# Micro_RC_Receiver.net
KiCad netlist of a schematic drawn in EAGLE
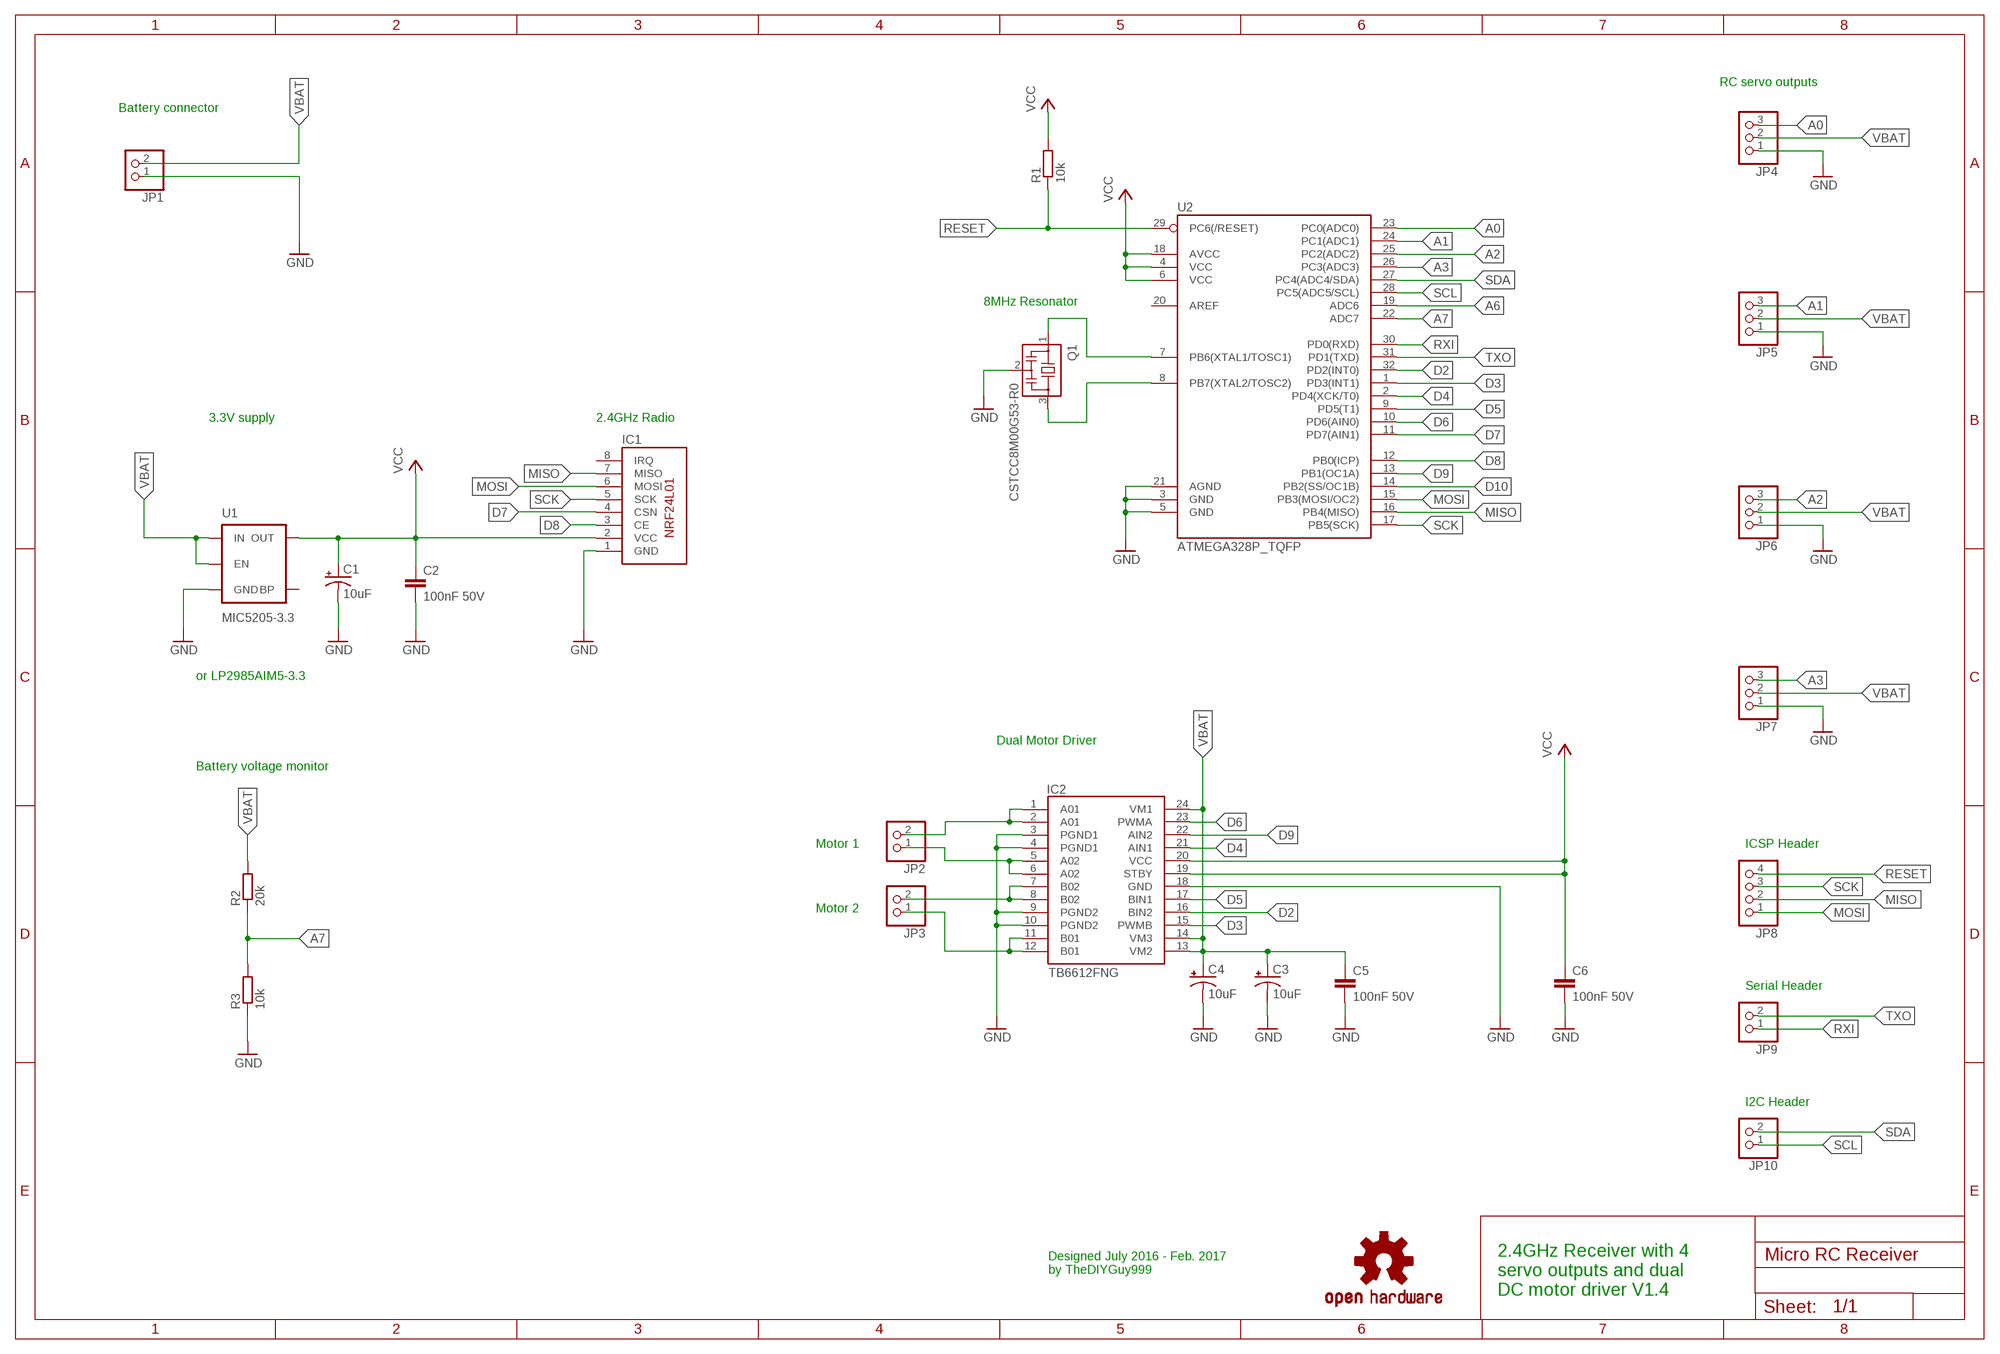
[diagram p0: schematic, sheet 1]

(export (version "E")
  (design (tool "Eeschema 10.0.6"))
  (components
    (comp (ref "C1")
      (value "10uF")
      (footprint "eagle-import:EIA3216")
      (libsource (lib "eagle-import") (part "10UF-16V-10%(TANT)"))
    )
    (comp (ref "C2")
      (value "100nF 50V")
      (footprint "eagle-import:C0805")
      (libsource (lib "eagle-import") (part "C-EUC0805"))
    )
    (comp (ref "C3")
      (value "10uF")
      (footprint "eagle-import:EIA3216")
      (libsource (lib "eagle-import") (part "10UF-16V-10%(TANT)"))
    )
    (comp (ref "C4")
      (value "10uF")
      (footprint "eagle-import:EIA3216")
      (libsource (lib "eagle-import") (part "10UF-16V-10%(TANT)"))
    )
    (comp (ref "C5")
      (value "100nF 50V")
      (footprint "eagle-import:C0805")
      (libsource (lib "eagle-import") (part "C-EUC0805"))
    )
    (comp (ref "C6")
      (value "100nF 50V")
      (footprint "eagle-import:C0805")
      (libsource (lib "eagle-import") (part "C-EUC0805"))
    )
    (comp (ref "IC1")
      (value "NRF24L01SMD")
      (footprint "eagle-import:NRF24L01_SMD")
      (libsource (lib "eagle-import") (part "NRF24L01SMD"))
    )
    (comp (ref "IC2")
      (value "TB6612FNG")
      (footprint "eagle-import:SSOP24")
      (libsource (lib "eagle-import") (part "TB6612FNG"))
    )
    (comp (ref "JP1")
      (value "PINHD-1X2")
      (footprint "eagle-import:1X02")
      (libsource (lib "eagle-import") (part "PINHD-1X2"))
    )
    (comp (ref "JP2")
      (value "PINHD-1X2")
      (footprint "eagle-import:1X02")
      (libsource (lib "eagle-import") (part "PINHD-1X2"))
    )
    (comp (ref "JP3")
      (value "PINHD-1X2")
      (footprint "eagle-import:1X02")
      (libsource (lib "eagle-import") (part "PINHD-1X2"))
    )
    (comp (ref "JP4")
      (value "PINHD-1X3")
      (footprint "eagle-import:1X03")
      (libsource (lib "eagle-import") (part "PINHD-1X3"))
    )
    (comp (ref "JP5")
      (value "PINHD-1X3")
      (footprint "eagle-import:1X03")
      (libsource (lib "eagle-import") (part "PINHD-1X3"))
    )
    (comp (ref "JP6")
      (value "PINHD-1X3")
      (footprint "eagle-import:1X03")
      (libsource (lib "eagle-import") (part "PINHD-1X3"))
    )
    (comp (ref "JP7")
      (value "PINHD-1X3")
      (footprint "eagle-import:1X03")
      (libsource (lib "eagle-import") (part "PINHD-1X3"))
    )
    (comp (ref "JP8")
      (value "PINHD-1X4")
      (footprint "eagle-import:1X04")
      (libsource (lib "eagle-import") (part "PINHD-1X4"))
    )
    (comp (ref "JP9")
      (value "PINHD-1X2")
      (footprint "eagle-import:1X02")
      (libsource (lib "eagle-import") (part "PINHD-1X2"))
    )
    (comp (ref "JP10")
      (value "PINHD-1X2")
      (footprint "eagle-import:1X02")
      (libsource (lib "eagle-import") (part "PINHD-1X2"))
    )
    (comp (ref "LOGO1")
      (value "OSHW-LOGOS")
      (footprint "eagle-import:OSHW-LOGO-S")
      (libsource (lib "eagle-import") (part "OSHW-LOGOS"))
    )
    (comp (ref "Q1")
      (value "CSTCC8M00G53-R0")
      (footprint "eagle-import:CSTCC")
      (libsource (lib "eagle-import") (part "CSTCC8M00G53-R0"))
    )
    (comp (ref "R1")
      (value "10k")
      (footprint "eagle-import:R0805")
      (libsource (lib "eagle-import") (part "R-EU_R0805"))
    )
    (comp (ref "R2")
      (value "20k")
      (footprint "eagle-import:R0805")
      (libsource (lib "eagle-import") (part "R-EU_R0805"))
    )
    (comp (ref "R3")
      (value "10k")
      (footprint "eagle-import:R0805")
      (libsource (lib "eagle-import") (part "R-EU_R0805"))
    )
    (comp (ref "U1")
      (value "MIC5205-3.3")
      (footprint "eagle-import:SOT23-5")
      (libsource (lib "eagle-import") (part "MIC52053.3V"))
    )
    (comp (ref "U2")
      (value "ATMEGA328P_TQFP")
      (footprint "eagle-import:TQFP32-08")
      (libsource (lib "eagle-import") (part "ATMEGA328P_TQFP"))
    )
  )
  (nets
    (net (code "1") (name "A0") (class "Default")
      (node (ref "JP4") (pin "3") (pinfunction "3_3") (pintype "passive"))
      (node (ref "U2") (pin "23") (pinfunction "PC0(ADC0)_23") (pintype "bidirectional"))
    )
    (net (code "2") (name "A1") (class "Default")
      (node (ref "JP5") (pin "3") (pinfunction "3_3") (pintype "passive"))
      (node (ref "U2") (pin "24") (pinfunction "PC1(ADC1)_24") (pintype "bidirectional"))
    )
    (net (code "3") (name "A2") (class "Default")
      (node (ref "JP6") (pin "3") (pinfunction "3_3") (pintype "passive"))
      (node (ref "U2") (pin "25") (pinfunction "PC2(ADC2)_25") (pintype "bidirectional"))
    )
    (net (code "4") (name "A3") (class "Default")
      (node (ref "JP7") (pin "3") (pinfunction "3_3") (pintype "passive"))
      (node (ref "U2") (pin "26") (pinfunction "PC3(ADC3)_26") (pintype "bidirectional"))
    )
    (net (code "5") (name "A6") (class "Default")
      (node (ref "U2") (pin "19") (pinfunction "ADC6_19") (pintype "bidirectional"))
    )
    (net (code "6") (name "A7") (class "Default")
      (node (ref "R2") (pin "1") (pinfunction "1_1") (pintype "passive"))
      (node (ref "R3") (pin "2") (pinfunction "2_2") (pintype "passive"))
      (node (ref "U2") (pin "22") (pinfunction "ADC7_22") (pintype "bidirectional"))
    )
    (net (code "7") (name "D2") (class "Default")
      (node (ref "IC2") (pin "16") (pinfunction "BIN2_16") (pintype "bidirectional"))
      (node (ref "U2") (pin "32") (pinfunction "PD2(INT0)_32") (pintype "bidirectional"))
    )
    (net (code "8") (name "D3") (class "Default")
      (node (ref "IC2") (pin "15") (pinfunction "PWMB_15") (pintype "bidirectional"))
      (node (ref "U2") (pin "1") (pinfunction "PD3(INT1)_1") (pintype "bidirectional"))
    )
    (net (code "9") (name "D4") (class "Default")
      (node (ref "IC2") (pin "21") (pinfunction "AIN1_21") (pintype "bidirectional"))
      (node (ref "U2") (pin "2") (pinfunction "PD4(XCK/T0)_2") (pintype "bidirectional"))
    )
    (net (code "10") (name "D5") (class "Default")
      (node (ref "IC2") (pin "17") (pinfunction "BIN1_17") (pintype "bidirectional"))
      (node (ref "U2") (pin "9") (pinfunction "PD5(T1)_9") (pintype "bidirectional"))
    )
    (net (code "11") (name "D6") (class "Default")
      (node (ref "IC2") (pin "23") (pinfunction "PWMA_23") (pintype "bidirectional"))
      (node (ref "U2") (pin "10") (pinfunction "PD6(AIN0)_10") (pintype "bidirectional"))
    )
    (net (code "12") (name "D7") (class "Default")
      (node (ref "IC1") (pin "4") (pinfunction "CSN_4") (pintype "bidirectional"))
      (node (ref "U2") (pin "11") (pinfunction "PD7(AIN1)_11") (pintype "bidirectional"))
    )
    (net (code "13") (name "D8") (class "Default")
      (node (ref "IC1") (pin "3") (pinfunction "CE_3") (pintype "bidirectional"))
      (node (ref "U2") (pin "12") (pinfunction "PB0(ICP)_12") (pintype "bidirectional"))
    )
    (net (code "14") (name "D9") (class "Default")
      (node (ref "IC2") (pin "22") (pinfunction "AIN2_22") (pintype "bidirectional"))
      (node (ref "U2") (pin "13") (pinfunction "PB1(OC1A)_13") (pintype "bidirectional"))
    )
    (net (code "15") (name "D10") (class "Default")
      (node (ref "U2") (pin "14") (pinfunction "PB2(SS/OC1B)_14") (pintype "bidirectional"))
    )
    (net (code "16") (name "GND") (class "Default")
      (node (ref "C1") (pin "C") (pinfunction "-_C") (pintype "passive"))
      (node (ref "C2") (pin "2") (pinfunction "2_2") (pintype "passive"))
      (node (ref "C3") (pin "C") (pinfunction "-_C") (pintype "passive"))
      (node (ref "C4") (pin "C") (pinfunction "-_C") (pintype "passive"))
      (node (ref "C5") (pin "2") (pinfunction "2_2") (pintype "passive"))
      (node (ref "C6") (pin "2") (pinfunction "2_2") (pintype "passive"))
      (node (ref "IC1") (pin "1") (pinfunction "GND_1") (pintype "bidirectional"))
      (node (ref "IC2") (pin "10") (pinfunction "PGND2_10") (pintype "bidirectional"))
      (node (ref "IC2") (pin "18") (pinfunction "GND_18") (pintype "bidirectional"))
      (node (ref "IC2") (pin "3") (pinfunction "PGND1_3") (pintype "bidirectional"))
      (node (ref "IC2") (pin "4") (pinfunction "PGND1_4") (pintype "bidirectional"))
      (node (ref "IC2") (pin "9") (pinfunction "PGND2_9") (pintype "bidirectional"))
      (node (ref "JP1") (pin "1") (pinfunction "1_1") (pintype "passive"))
      (node (ref "JP4") (pin "1") (pinfunction "1_1") (pintype "passive"))
      (node (ref "JP5") (pin "1") (pinfunction "1_1") (pintype "passive"))
      (node (ref "JP6") (pin "1") (pinfunction "1_1") (pintype "passive"))
      (node (ref "JP7") (pin "1") (pinfunction "1_1") (pintype "passive"))
      (node (ref "Q1") (pin "2") (pinfunction "2_2") (pintype "passive"))
      (node (ref "R3") (pin "1") (pinfunction "1_1") (pintype "passive"))
      (node (ref "U1") (pin "2") (pinfunction "GND_2") (pintype "input"))
      (node (ref "U2") (pin "21") (pinfunction "AGND_21") (pintype "bidirectional"))
      (node (ref "U2") (pin "3") (pinfunction "GND_3") (pintype "bidirectional"))
      (node (ref "U2") (pin "5") (pinfunction "GND_5") (pintype "bidirectional"))
    )
    (net (code "17") (name "MISO") (class "Default")
      (node (ref "IC1") (pin "7") (pinfunction "MISO_7") (pintype "bidirectional"))
      (node (ref "JP8") (pin "2") (pinfunction "2_2") (pintype "passive"))
      (node (ref "U2") (pin "16") (pinfunction "PB4(MISO)_16") (pintype "bidirectional"))
    )
    (net (code "18") (name "MOSI") (class "Default")
      (node (ref "IC1") (pin "6") (pinfunction "MOSI_6") (pintype "bidirectional"))
      (node (ref "JP8") (pin "1") (pinfunction "1_1") (pintype "passive"))
      (node (ref "U2") (pin "15") (pinfunction "PB3(MOSI/OC2)_15") (pintype "bidirectional"))
    )
    (net (code "19") (name "Net-(IC2-A01-Pad1)") (class "Default")
      (node (ref "IC2") (pin "1") (pinfunction "A01_1") (pintype "bidirectional"))
      (node (ref "IC2") (pin "2") (pinfunction "A01_2") (pintype "bidirectional"))
      (node (ref "JP2") (pin "2") (pinfunction "2_2") (pintype "passive"))
    )
    (net (code "20") (name "Net-(IC2-A02-Pad5)") (class "Default")
      (node (ref "IC2") (pin "5") (pinfunction "A02_5") (pintype "bidirectional"))
      (node (ref "IC2") (pin "6") (pinfunction "A02_6") (pintype "bidirectional"))
      (node (ref "JP2") (pin "1") (pinfunction "1_1") (pintype "passive"))
    )
    (net (code "21") (name "Net-(IC2-B01-Pad11)") (class "Default")
      (node (ref "IC2") (pin "11") (pinfunction "B01_11") (pintype "bidirectional"))
      (node (ref "IC2") (pin "12") (pinfunction "B01_12") (pintype "bidirectional"))
      (node (ref "JP3") (pin "1") (pinfunction "1_1") (pintype "passive"))
    )
    (net (code "22") (name "Net-(IC2-B02-Pad7)") (class "Default")
      (node (ref "IC2") (pin "7") (pinfunction "B02_7") (pintype "bidirectional"))
      (node (ref "IC2") (pin "8") (pinfunction "B02_8") (pintype "bidirectional"))
      (node (ref "JP3") (pin "2") (pinfunction "2_2") (pintype "passive"))
    )
    (net (code "23") (name "Net-(U2-PB6(XTAL1{slash}TOSC1))") (class "Default")
      (node (ref "Q1") (pin "1") (pinfunction "1_1") (pintype "passive"))
      (node (ref "U2") (pin "7") (pinfunction "PB6(XTAL1/TOSC1)_7") (pintype "bidirectional"))
    )
    (net (code "24") (name "Net-(U2-PB7(XTAL2{slash}TOSC2))") (class "Default")
      (node (ref "Q1") (pin "3") (pinfunction "3_3") (pintype "passive"))
      (node (ref "U2") (pin "8") (pinfunction "PB7(XTAL2/TOSC2)_8") (pintype "bidirectional"))
    )
    (net (code "25") (name "RESET") (class "Default")
      (node (ref "JP8") (pin "4") (pinfunction "4_4") (pintype "passive"))
      (node (ref "R1") (pin "1") (pinfunction "1_1") (pintype "passive"))
      (node (ref "U2") (pin "29") (pinfunction "PC6(/RESET)_29") (pintype "bidirectional"))
    )
    (net (code "26") (name "RXI") (class "Default")
      (node (ref "JP9") (pin "1") (pinfunction "1_1") (pintype "passive"))
      (node (ref "U2") (pin "30") (pinfunction "PD0(RXD)_30") (pintype "bidirectional"))
    )
    (net (code "27") (name "SCK") (class "Default")
      (node (ref "IC1") (pin "5") (pinfunction "SCK_5") (pintype "bidirectional"))
      (node (ref "JP8") (pin "3") (pinfunction "3_3") (pintype "passive"))
      (node (ref "U2") (pin "17") (pinfunction "PB5(SCK)_17") (pintype "bidirectional"))
    )
    (net (code "28") (name "SCL") (class "Default")
      (node (ref "JP10") (pin "1") (pinfunction "1_1") (pintype "passive"))
      (node (ref "U2") (pin "28") (pinfunction "PC5(ADC5/SCL)_28") (pintype "bidirectional"))
    )
    (net (code "29") (name "SDA") (class "Default")
      (node (ref "JP10") (pin "2") (pinfunction "2_2") (pintype "passive"))
      (node (ref "U2") (pin "27") (pinfunction "PC4(ADC4/SDA)_27") (pintype "bidirectional"))
    )
    (net (code "30") (name "TXO") (class "Default")
      (node (ref "JP9") (pin "2") (pinfunction "2_2") (pintype "passive"))
      (node (ref "U2") (pin "31") (pinfunction "PD1(TXD)_31") (pintype "bidirectional"))
    )
    (net (code "31") (name "VBAT") (class "Default")
      (node (ref "C3") (pin "A") (pinfunction "+_A") (pintype "passive"))
      (node (ref "C4") (pin "A") (pinfunction "+_A") (pintype "passive"))
      (node (ref "C5") (pin "1") (pinfunction "1_1") (pintype "passive"))
      (node (ref "IC2") (pin "13") (pinfunction "VM2_13") (pintype "bidirectional"))
      (node (ref "IC2") (pin "14") (pinfunction "VM3_14") (pintype "bidirectional"))
      (node (ref "IC2") (pin "24") (pinfunction "VM1_24") (pintype "bidirectional"))
      (node (ref "JP1") (pin "2") (pinfunction "2_2") (pintype "passive"))
      (node (ref "JP4") (pin "2") (pinfunction "2_2") (pintype "passive"))
      (node (ref "JP5") (pin "2") (pinfunction "2_2") (pintype "passive"))
      (node (ref "JP6") (pin "2") (pinfunction "2_2") (pintype "passive"))
      (node (ref "JP7") (pin "2") (pinfunction "2_2") (pintype "passive"))
      (node (ref "R2") (pin "2") (pinfunction "2_2") (pintype "passive"))
      (node (ref "U1") (pin "1") (pinfunction "IN_1") (pintype "input"))
      (node (ref "U1") (pin "3") (pinfunction "EN_3") (pintype "input"))
    )
    (net (code "32") (name "VCC") (class "Default")
      (node (ref "C1") (pin "A") (pinfunction "+_A") (pintype "passive"))
      (node (ref "C2") (pin "1") (pinfunction "1_1") (pintype "passive"))
      (node (ref "C6") (pin "1") (pinfunction "1_1") (pintype "passive"))
      (node (ref "IC1") (pin "2") (pinfunction "VCC_2") (pintype "bidirectional"))
      (node (ref "IC2") (pin "19") (pinfunction "STBY_19") (pintype "bidirectional"))
      (node (ref "IC2") (pin "20") (pinfunction "VCC_20") (pintype "bidirectional"))
      (node (ref "R1") (pin "2") (pinfunction "2_2") (pintype "passive"))
      (node (ref "U1") (pin "5") (pinfunction "OUT_5") (pintype "passive"))
      (node (ref "U2") (pin "18") (pinfunction "AVCC_18") (pintype "bidirectional"))
      (node (ref "U2") (pin "4") (pinfunction "VCC_4") (pintype "bidirectional"))
      (node (ref "U2") (pin "6") (pinfunction "VCC_6") (pintype "bidirectional"))
    )
    (net (code "33") (name "unconnected-(IC1-IRQ-Pad8)") (class "Default")
      (node (ref "IC1") (pin "8") (pinfunction "IRQ_8") (pintype "bidirectional"))
    )
    (net (code "34") (name "unconnected-(U1-BP-Pad4)") (class "Default")
      (node (ref "U1") (pin "4") (pinfunction "BP_4") (pintype "input"))
    )
    (net (code "35") (name "unconnected-(U2-AREF-Pad20)") (class "Default")
      (node (ref "U2") (pin "20") (pinfunction "AREF_20") (pintype "bidirectional"))
    )
  )
)
